# nGeigie_upper_boardV1_00.net
KiCad netlist of a schematic drawn in EAGLE
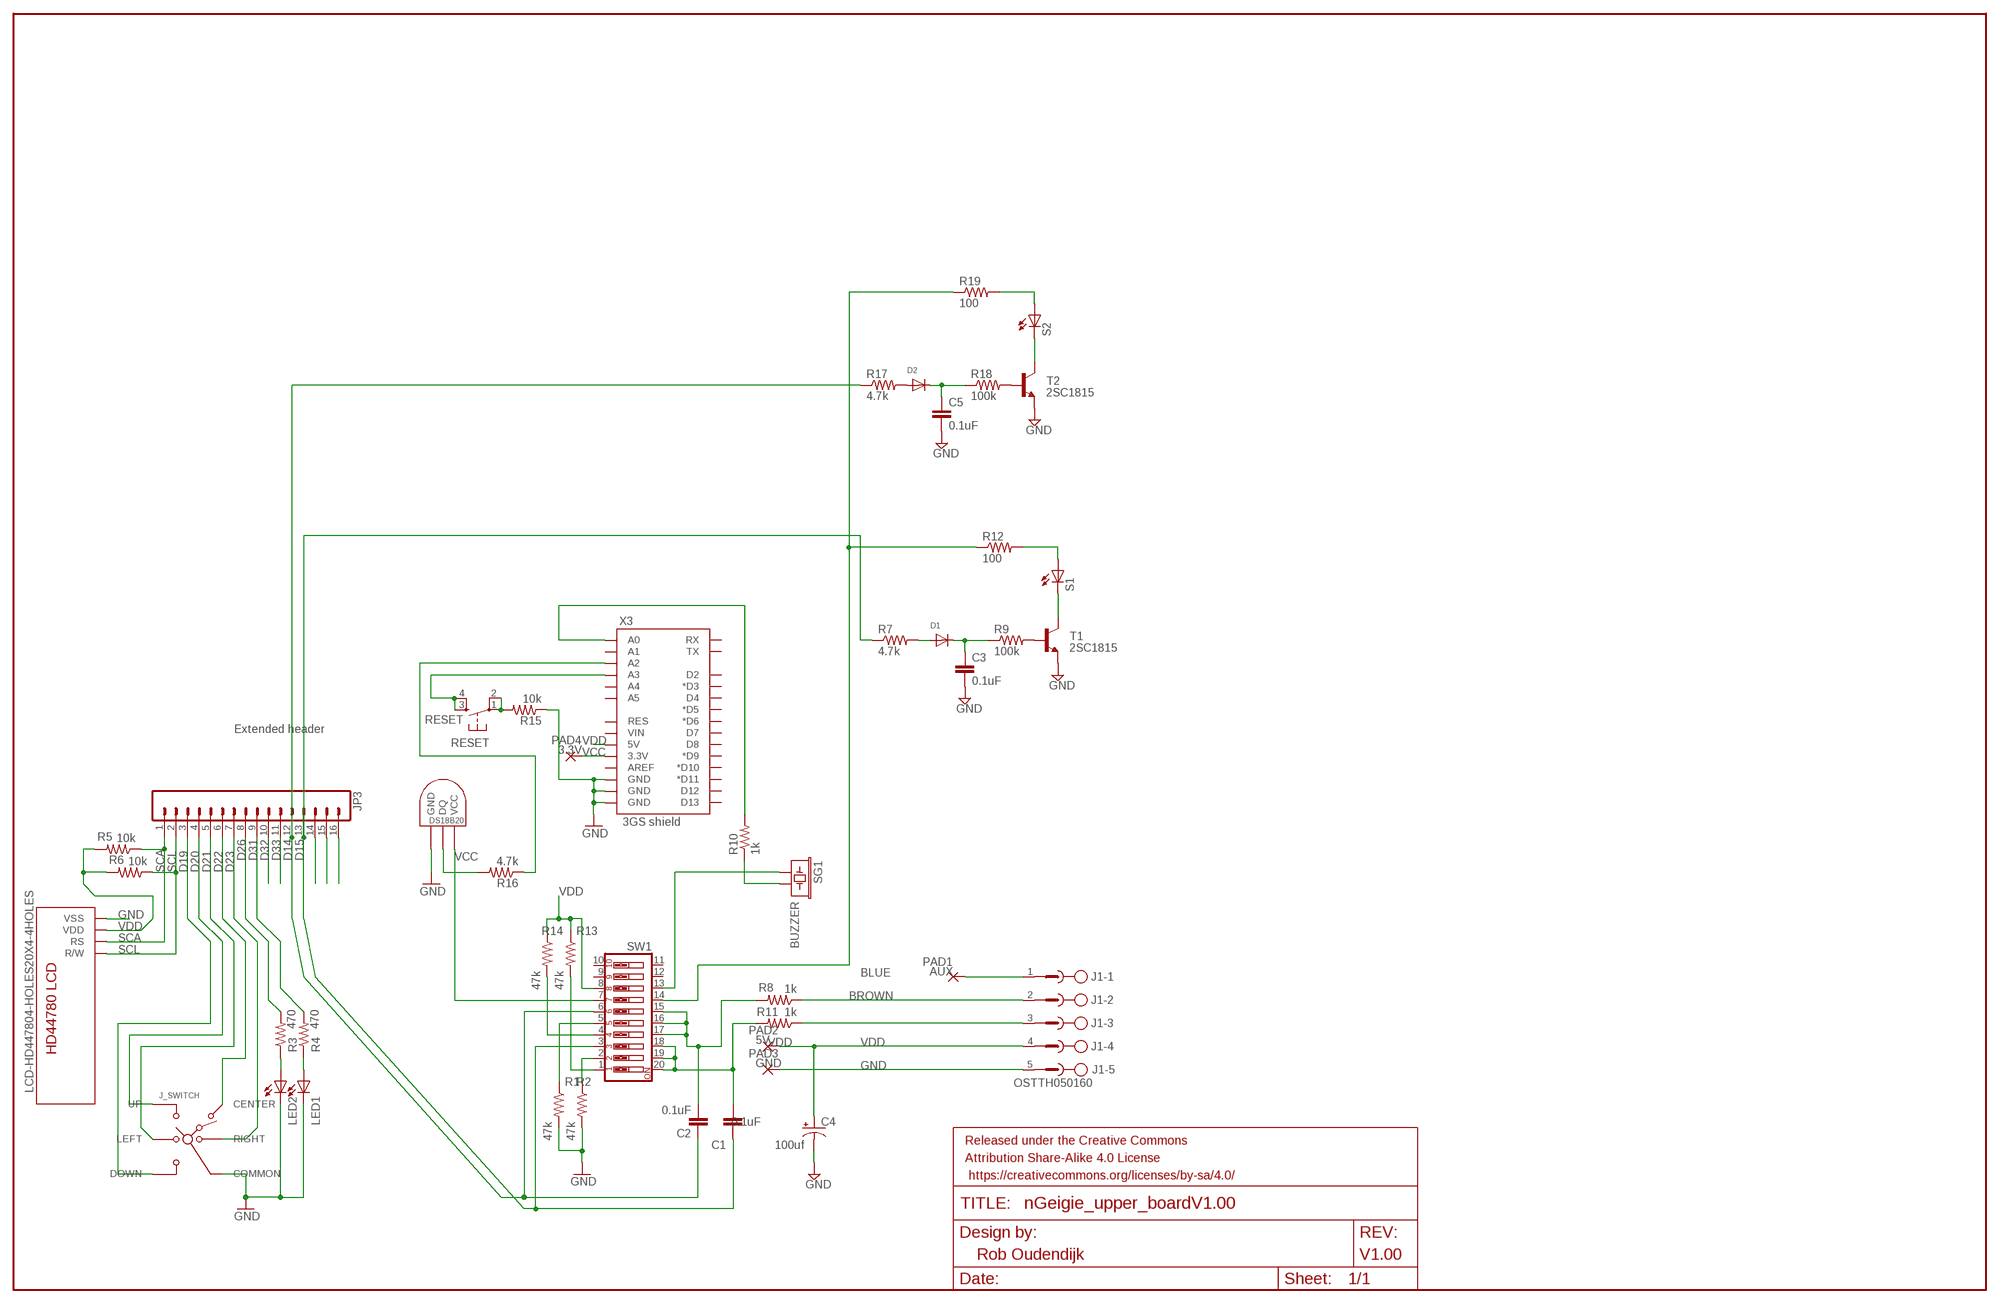
[diagram p0: schematic, sheet 1]

(export (version "E")
  (design (tool "Eeschema 10.0.6"))
  (components
    (comp (ref "C1")
      (value "0.1uF")
      (footprint "eagle-import:C025-024X044")
      (libsource (lib "eagle-import") (part "C-EU025-024X044"))
    )
    (comp (ref "C2")
      (value "0.1uF")
      (footprint "eagle-import:C025-024X044")
      (libsource (lib "eagle-import") (part "C-EU025-024X044"))
    )
    (comp (ref "C3")
      (value "0.1uF")
      (footprint "eagle-import:C025-024X044")
      (libsource (lib "eagle-import") (part "C-EU025-024X044"))
    )
    (comp (ref "C4")
      (value "100uf")
      (footprint "eagle-import:CPOL-RADIAL-100UF-25V")
      (libsource (lib "eagle-import") (part "CAP_POLPTH1"))
    )
    (comp (ref "C5")
      (value "0.1uF")
      (footprint "eagle-import:C025-024X044")
      (libsource (lib "eagle-import") (part "C-EU025-024X044"))
    )
    (comp (ref "D1")
      (value "DIODEDIODE_BIG")
      (footprint "eagle-import:DO41-10")
      (libsource (lib "eagle-import") (part "DIODEDIODE_BIG"))
    )
    (comp (ref "D2")
      (value "DIODEDIODE_BIG")
      (footprint "eagle-import:DO41-10")
      (libsource (lib "eagle-import") (part "DIODEDIODE_BIG"))
    )
    (comp (ref "FRAME1")
      (value "FRAME-LEDGER")
      (footprint "eagle-import:CREATIVE_COMMONS")
      (libsource (lib "eagle-import") (part "FRAME-LEDGER"))
    )
    (comp (ref "J1")
      (value "OSTTH050160")
      (footprint "eagle-import:EDSTL130-05")
      (libsource (lib "eagle-import") (part "OSTTH050160"))
    )
    (comp (ref "JP3")
      (value "Extended header")
      (footprint "eagle-import:1X16")
      (libsource (lib "eagle-import") (part "M16PTH"))
    )
    (comp (ref "J_SWITCH")
      (value "SKQUCAA010")
      (footprint "eagle-import:SKQU")
      (fields (field (name "MF") "ALPS"))
      (libsource (lib "eagle-import") (part "SKQUCAA010"))
    )
    (comp (ref "LED1")
      (value "LED3MM")
      (footprint "eagle-import:LED3MM")
      (libsource (lib "eagle-import") (part "LED3MM"))
    )
    (comp (ref "LED2")
      (value "LED3MM")
      (footprint "eagle-import:LED3MM")
      (libsource (lib "eagle-import") (part "LED3MM"))
    )
    (comp (ref "PAD1")
      (value "AUX")
      (footprint "eagle-import:2,15_1,0")
      (libsource (lib "eagle-import") (part "2,15/1,0"))
    )
    (comp (ref "PAD2")
      (value "5V")
      (footprint "eagle-import:2,15_1,0")
      (libsource (lib "eagle-import") (part "2,15/1,0"))
    )
    (comp (ref "PAD3")
      (value "GND")
      (footprint "eagle-import:2,15_1,0")
      (libsource (lib "eagle-import") (part "2,15/1,0"))
    )
    (comp (ref "PAD4")
      (value "3.3V")
      (footprint "eagle-import:2,15_1,0")
      (libsource (lib "eagle-import") (part "2,15/1,0"))
    )
    (comp (ref "R1")
      (value "47k")
      (footprint "eagle-import:0207_10")
      (libsource (lib "eagle-import") (part "resistor_R-US_0207/10"))
    )
    (comp (ref "R2")
      (value "47k")
      (footprint "eagle-import:0207_10")
      (libsource (lib "eagle-import") (part "resistor_R-US_0207/10"))
    )
    (comp (ref "R3")
      (value "470")
      (footprint "eagle-import:0207_10")
      (libsource (lib "eagle-import") (part "resistor_R-US_0207/10"))
    )
    (comp (ref "R4")
      (value "470")
      (footprint "eagle-import:0207_10")
      (libsource (lib "eagle-import") (part "resistor_R-US_0207/10"))
    )
    (comp (ref "R5")
      (value "10k")
      (footprint "eagle-import:0207_10")
      (libsource (lib "eagle-import") (part "R-US_0207/10"))
    )
    (comp (ref "R6")
      (value "10k")
      (footprint "eagle-import:0207_10")
      (libsource (lib "eagle-import") (part "R-US_0207/10"))
    )
    (comp (ref "R7")
      (value "4.7k")
      (footprint "eagle-import:0207_10")
      (libsource (lib "eagle-import") (part "rcl_R-US_0207/10"))
    )
    (comp (ref "R8")
      (value "1k")
      (footprint "eagle-import:0207_10")
      (libsource (lib "eagle-import") (part "resistor_R-US_0207/10"))
    )
    (comp (ref "R9")
      (value "100k")
      (footprint "eagle-import:0207_10")
      (libsource (lib "eagle-import") (part "rcl_R-US_0207/10"))
    )
    (comp (ref "R10")
      (value "1k")
      (footprint "eagle-import:0207_10")
      (libsource (lib "eagle-import") (part "resistor_R-US_0207/10"))
    )
    (comp (ref "R11")
      (value "1k")
      (footprint "eagle-import:0207_10")
      (libsource (lib "eagle-import") (part "resistor_R-US_0207/10"))
    )
    (comp (ref "R12")
      (value "100")
      (footprint "eagle-import:0207_10")
      (libsource (lib "eagle-import") (part "rcl_R-US_0207/10"))
    )
    (comp (ref "R13")
      (value "47k")
      (footprint "eagle-import:0207_10")
      (libsource (lib "eagle-import") (part "resistor_R-US_0207/10"))
    )
    (comp (ref "R14")
      (value "47k")
      (footprint "eagle-import:0207_10")
      (libsource (lib "eagle-import") (part "resistor_R-US_0207/10"))
    )
    (comp (ref "R15")
      (value "10k")
      (footprint "eagle-import:0207_10")
      (libsource (lib "eagle-import") (part "resistor_R-US_0207/10"))
    )
    (comp (ref "R16")
      (value "4.7k")
      (footprint "eagle-import:0207_10")
      (libsource (lib "eagle-import") (part "resistor_R-US_0207/10"))
    )
    (comp (ref "R17")
      (value "4.7k")
      (footprint "eagle-import:0207_10")
      (libsource (lib "eagle-import") (part "rcl_R-US_0207/10"))
    )
    (comp (ref "R18")
      (value "100k")
      (footprint "eagle-import:0207_10")
      (libsource (lib "eagle-import") (part "rcl_R-US_0207/10"))
    )
    (comp (ref "R19")
      (value "100")
      (footprint "eagle-import:0207_10")
      (libsource (lib "eagle-import") (part "rcl_R-US_0207/10"))
    )
    (comp (ref "RESET")
      (value "RESET")
      (footprint "eagle-import:DTS-6")
      (libsource (lib "eagle-import") (part "DTS-6"))
    )
    (comp (ref "S1")
      (value "LED3MM")
      (footprint "eagle-import:LED3MM")
      (libsource (lib "eagle-import") (part "LED3MM"))
    )
    (comp (ref "S2")
      (value "LED3MM")
      (footprint "eagle-import:LED3MM")
      (libsource (lib "eagle-import") (part "LED3MM"))
    )
    (comp (ref "SG1")
      (value "BUZZER")
      (footprint "eagle-import:BUZZER-12MM")
      (libsource (lib "eagle-import") (part "BUZZERPTH"))
    )
    (comp (ref "SW1")
      (value "SW_DIP-10")
      (footprint "eagle-import:EDG-10")
      (libsource (lib "eagle-import") (part "SW_DIP-10"))
    )
    (comp (ref "T1")
      (value "2SC1815")
      (footprint "eagle-import:TO92-ECB")
      (libsource (lib "eagle-import") (part "2SC1815"))
    )
    (comp (ref "T2")
      (value "2SC1815")
      (footprint "eagle-import:TO92-ECB")
      (libsource (lib "eagle-import") (part "2SC1815"))
    )
    (comp (ref "TEMP")
      (value "AVA_DS1820TO92")
      (footprint "eagle-import:AVA_DS1820")
      (libsource (lib "eagle-import") (part "AVA_DS1820TO92"))
    )
    (comp (ref "X1")
      (value "LCD-HD447804-HOLES20X4-4HOLES")
      (footprint "eagle-import:LCD-20X4-4HOLES")
      (libsource (lib "eagle-import") (part "LCD-HD4478020X4-4HOLES4-HOLES"))
    )
    (comp (ref "X3")
      (value "3GS shield")
      (footprint "eagle-import:DUEMILANOVE_SHIELD")
      (libsource (lib "eagle-import") (part "ARDUINO_SHIELDLABEL"))
    )
  )
  (nets
    (net (code "1") (name "/BLUE") (class "Default")
      (node (ref "J1") (pin "2") (pinfunction "SK_2") (pintype "passive"))
      (node (ref "R8") (pin "1") (pinfunction "1_1") (pintype "passive"))
    )
    (net (code "2") (name "/BROWN") (class "Default")
      (node (ref "J1") (pin "3") (pinfunction "SK_3") (pintype "passive"))
      (node (ref "R11") (pin "1") (pinfunction "1_1") (pintype "passive"))
    )
    (net (code "3") (name "/D14") (class "Default")
      (node (ref "C2") (pin "1") (pinfunction "1_1") (pintype "passive"))
      (node (ref "JP3") (pin "12") (pinfunction "12_12") (pintype "passive"))
      (node (ref "R17") (pin "1") (pinfunction "1_1") (pintype "passive"))
      (node (ref "SW1") (pin "6") (pinfunction "6_6") (pintype "passive"))
    )
    (net (code "4") (name "/D15") (class "Default")
      (node (ref "C1") (pin "1") (pinfunction "1_1") (pintype "passive"))
      (node (ref "JP3") (pin "13") (pinfunction "13_13") (pintype "passive"))
      (node (ref "R7") (pin "1") (pinfunction "1_1") (pintype "passive"))
      (node (ref "SW1") (pin "3") (pinfunction "3_3") (pintype "passive"))
    )
    (net (code "5") (name "/D19") (class "Default")
      (node (ref "JP3") (pin "3") (pinfunction "3_3") (pintype "passive"))
      (node (ref "J_SWITCH") (pin "DOWN") (pinfunction "DOWN_DOWN") (pintype "passive"))
    )
    (net (code "6") (name "/D20") (class "Default")
      (node (ref "JP3") (pin "4") (pinfunction "4_4") (pintype "passive"))
      (node (ref "J_SWITCH") (pin "UP") (pinfunction "UP_UP") (pintype "passive"))
    )
    (net (code "7") (name "/D21") (class "Default")
      (node (ref "JP3") (pin "5") (pinfunction "5_5") (pintype "passive"))
      (node (ref "J_SWITCH") (pin "LEFT") (pinfunction "LEFT_LEFT") (pintype "passive"))
    )
    (net (code "8") (name "/D22") (class "Default")
      (node (ref "JP3") (pin "6") (pinfunction "6_6") (pintype "passive"))
      (node (ref "J_SWITCH") (pin "CENTER") (pinfunction "CENTER_CENTER") (pintype "passive"))
    )
    (net (code "9") (name "/D23") (class "Default")
      (node (ref "JP3") (pin "7") (pinfunction "7_7") (pintype "passive"))
      (node (ref "J_SWITCH") (pin "RIGHT") (pinfunction "RIGHT_RIGHT") (pintype "passive"))
    )
    (net (code "10") (name "/D26") (class "Default")
      (node (ref "JP3") (pin "8") (pinfunction "8_8") (pintype "passive"))
      (node (ref "R3") (pin "2") (pinfunction "2_2") (pintype "passive"))
    )
    (net (code "11") (name "/D31") (class "Default")
      (node (ref "JP3") (pin "9") (pinfunction "9_9") (pintype "passive"))
      (node (ref "R4") (pin "2") (pinfunction "2_2") (pintype "passive"))
    )
    (net (code "12") (name "/D32") (class "Default")
      (node (ref "JP3") (pin "10") (pinfunction "10_10") (pintype "passive"))
    )
    (net (code "13") (name "/D33") (class "Default")
      (node (ref "JP3") (pin "11") (pinfunction "11_11") (pintype "passive"))
    )
    (net (code "14") (name "/SCA") (class "Default")
      (node (ref "JP3") (pin "1") (pinfunction "1_1") (pintype "passive"))
      (node (ref "R5") (pin "1") (pinfunction "1_1") (pintype "passive"))
      (node (ref "X1") (pin "P$15") (pinfunction "RS_P$15") (pintype "input"))
    )
    (net (code "15") (name "/SCL") (class "Default")
      (node (ref "JP3") (pin "2") (pinfunction "2_2") (pintype "passive"))
      (node (ref "R6") (pin "1") (pinfunction "1_1") (pintype "passive"))
      (node (ref "X1") (pin "P$16") (pinfunction "R/W_P$16") (pintype "input"))
    )
    (net (code "16") (name "/VCC") (class "Default")
      (node (ref "PAD4") (pin "1") (pinfunction "P_1") (pintype "passive"))
      (node (ref "SW1") (pin "7") (pinfunction "7_7") (pintype "passive"))
      (node (ref "TEMP") (pin "VDD") (pinfunction "VCC_VDD") (pintype "power_in"))
      (node (ref "X3") (pin "3.3V") (pinfunction "3.3V_3.3V") (pintype "bidirectional"))
    )
    (net (code "17") (name "/VDD") (class "Default")
      (node (ref "C4") (pin "2") (pinfunction "+_2") (pintype "passive"))
      (node (ref "J1") (pin "4") (pinfunction "SK_4") (pintype "passive"))
      (node (ref "PAD2") (pin "1") (pinfunction "P_1") (pintype "passive"))
      (node (ref "R13") (pin "1") (pinfunction "1_1") (pintype "passive"))
      (node (ref "R14") (pin "1") (pinfunction "1_1") (pintype "passive"))
      (node (ref "R5") (pin "2") (pinfunction "2_2") (pintype "passive"))
      (node (ref "R6") (pin "2") (pinfunction "2_2") (pintype "passive"))
      (node (ref "SW1") (pin "8") (pinfunction "8_8") (pintype "passive"))
      (node (ref "X1") (pin "P$14") (pinfunction "VDD_P$14") (pintype "power_in"))
      (node (ref "X3") (pin "5V") (pinfunction "5V_5V") (pintype "bidirectional"))
    )
    (net (code "18") (name "GND") (class "Default")
      (node (ref "C3") (pin "2") (pinfunction "2_2") (pintype "passive"))
      (node (ref "C4") (pin "1") (pinfunction "-_1") (pintype "passive"))
      (node (ref "C5") (pin "2") (pinfunction "2_2") (pintype "passive"))
      (node (ref "J1") (pin "5") (pinfunction "SK_5") (pintype "passive"))
      (node (ref "J_SWITCH") (pin "COMMON") (pinfunction "COMMON_COMMON") (pintype "power_in"))
      (node (ref "LED1") (pin "K") (pinfunction "C_K") (pintype "passive"))
      (node (ref "LED2") (pin "K") (pinfunction "C_K") (pintype "passive"))
      (node (ref "PAD3") (pin "1") (pinfunction "P_1") (pintype "passive"))
      (node (ref "R1") (pin "2") (pinfunction "2_2") (pintype "passive"))
      (node (ref "R15") (pin "1") (pinfunction "1_1") (pintype "passive"))
      (node (ref "R2") (pin "2") (pinfunction "2_2") (pintype "passive"))
      (node (ref "T1") (pin "E") (pinfunction "E_E") (pintype "passive"))
      (node (ref "T2") (pin "E") (pinfunction "E_E") (pintype "passive"))
      (node (ref "TEMP") (pin "GND") (pinfunction "GND_GND") (pintype "power_in"))
      (node (ref "X1") (pin "P$13") (pinfunction "VSS_P$13") (pintype "power_in"))
      (node (ref "X3") (pin "GND@0") (pinfunction "GND_GND@0") (pintype "bidirectional"))
      (node (ref "X3") (pin "GND@1") (pinfunction "GND_GND@1") (pintype "bidirectional"))
      (node (ref "X3") (pin "GND@2") (pinfunction "GND_GND@2") (pintype "bidirectional"))
    )
    (net (code "19") (name "Net-(C1-Pad2)") (class "Default")
      (node (ref "C1") (pin "2") (pinfunction "2_2") (pintype "passive"))
      (node (ref "R11") (pin "2") (pinfunction "2_2") (pintype "passive"))
      (node (ref "SW1") (pin "18") (pinfunction "18_18") (pintype "passive"))
      (node (ref "SW1") (pin "19") (pinfunction "19_19") (pintype "passive"))
      (node (ref "SW1") (pin "20") (pinfunction "20_20") (pintype "passive"))
    )
    (net (code "20") (name "Net-(C2-Pad2)") (class "Default")
      (node (ref "C2") (pin "2") (pinfunction "2_2") (pintype "passive"))
      (node (ref "R8") (pin "2") (pinfunction "2_2") (pintype "passive"))
      (node (ref "SW1") (pin "15") (pinfunction "15_15") (pintype "passive"))
      (node (ref "SW1") (pin "16") (pinfunction "16_16") (pintype "passive"))
      (node (ref "SW1") (pin "17") (pinfunction "17_17") (pintype "passive"))
    )
    (net (code "21") (name "Net-(C3-Pad1)") (class "Default")
      (node (ref "C3") (pin "1") (pinfunction "1_1") (pintype "passive"))
      (node (ref "D1") (pin "C") (pinfunction "C_C") (pintype "passive"))
      (node (ref "R9") (pin "1") (pinfunction "1_1") (pintype "passive"))
    )
    (net (code "22") (name "Net-(C5-Pad1)") (class "Default")
      (node (ref "C5") (pin "1") (pinfunction "1_1") (pintype "passive"))
      (node (ref "D2") (pin "C") (pinfunction "C_C") (pintype "passive"))
      (node (ref "R18") (pin "1") (pinfunction "1_1") (pintype "passive"))
    )
    (net (code "23") (name "Net-(D1-PadA)") (class "Default")
      (node (ref "D1") (pin "A") (pinfunction "A_A") (pintype "passive"))
      (node (ref "R7") (pin "2") (pinfunction "2_2") (pintype "passive"))
    )
    (net (code "24") (name "Net-(D2-PadA)") (class "Default")
      (node (ref "D2") (pin "A") (pinfunction "A_A") (pintype "passive"))
      (node (ref "R17") (pin "2") (pinfunction "2_2") (pintype "passive"))
    )
    (net (code "25") (name "Net-(J1A-SK)") (class "Default")
      (node (ref "J1") (pin "1") (pinfunction "SK_1") (pintype "passive"))
      (node (ref "PAD1") (pin "1") (pinfunction "P_1") (pintype "passive"))
    )
    (net (code "26") (name "Net-(LED1-PadA)") (class "Default")
      (node (ref "LED1") (pin "A") (pinfunction "A_A") (pintype "passive"))
      (node (ref "R4") (pin "1") (pinfunction "1_1") (pintype "passive"))
    )
    (net (code "27") (name "Net-(LED2-PadA)") (class "Default")
      (node (ref "LED2") (pin "A") (pinfunction "A_A") (pintype "passive"))
      (node (ref "R3") (pin "1") (pinfunction "1_1") (pintype "passive"))
    )
    (net (code "28") (name "Net-(R1-Pad1)") (class "Default")
      (node (ref "R1") (pin "1") (pinfunction "1_1") (pintype "passive"))
      (node (ref "SW1") (pin "5") (pinfunction "5_5") (pintype "passive"))
    )
    (net (code "29") (name "Net-(R2-Pad1)") (class "Default")
      (node (ref "R2") (pin "1") (pinfunction "1_1") (pintype "passive"))
      (node (ref "SW1") (pin "2") (pinfunction "2_2") (pintype "passive"))
    )
    (net (code "30") (name "Net-(R9-Pad2)") (class "Default")
      (node (ref "R9") (pin "2") (pinfunction "2_2") (pintype "passive"))
      (node (ref "T1") (pin "B") (pinfunction "B_B") (pintype "passive"))
    )
    (net (code "31") (name "Net-(R10-Pad2)") (class "Default")
      (node (ref "R10") (pin "2") (pinfunction "2_2") (pintype "passive"))
      (node (ref "X3") (pin "A0") (pinfunction "A0_A0") (pintype "bidirectional"))
    )
    (net (code "32") (name "Net-(R12-Pad1)") (class "Default")
      (node (ref "R12") (pin "1") (pinfunction "1_1") (pintype "passive"))
      (node (ref "R19") (pin "1") (pinfunction "1_1") (pintype "passive"))
      (node (ref "SW1") (pin "14") (pinfunction "14_14") (pintype "passive"))
    )
    (net (code "33") (name "Net-(R12-Pad2)") (class "Default")
      (node (ref "R12") (pin "2") (pinfunction "2_2") (pintype "passive"))
      (node (ref "S1") (pin "A") (pinfunction "A_A") (pintype "passive"))
    )
    (net (code "34") (name "Net-(R13-Pad2)") (class "Default")
      (node (ref "R13") (pin "2") (pinfunction "2_2") (pintype "passive"))
      (node (ref "SW1") (pin "1") (pinfunction "1_1") (pintype "passive"))
    )
    (net (code "35") (name "Net-(R14-Pad2)") (class "Default")
      (node (ref "R14") (pin "2") (pinfunction "2_2") (pintype "passive"))
      (node (ref "SW1") (pin "4") (pinfunction "4_4") (pintype "passive"))
    )
    (net (code "36") (name "Net-(R15-Pad2)") (class "Default")
      (node (ref "R15") (pin "2") (pinfunction "2_2") (pintype "passive"))
      (node (ref "RESET") (pin "1") (pinfunction "1_1") (pintype "passive"))
      (node (ref "RESET") (pin "2") (pinfunction "2_2") (pintype "passive"))
    )
    (net (code "37") (name "Net-(R16-Pad1)") (class "Default")
      (node (ref "R16") (pin "1") (pinfunction "1_1") (pintype "passive"))
      (node (ref "X3") (pin "A2") (pinfunction "A2_A2") (pintype "bidirectional"))
    )
    (net (code "38") (name "Net-(R16-Pad2)") (class "Default")
      (node (ref "R16") (pin "2") (pinfunction "2_2") (pintype "passive"))
      (node (ref "TEMP") (pin "DQ") (pinfunction "DQ_DQ") (pintype "bidirectional"))
    )
    (net (code "39") (name "Net-(R18-Pad2)") (class "Default")
      (node (ref "R18") (pin "2") (pinfunction "2_2") (pintype "passive"))
      (node (ref "T2") (pin "B") (pinfunction "B_B") (pintype "passive"))
    )
    (net (code "40") (name "Net-(R19-Pad2)") (class "Default")
      (node (ref "R19") (pin "2") (pinfunction "2_2") (pintype "passive"))
      (node (ref "S2") (pin "A") (pinfunction "A_A") (pintype "passive"))
    )
    (net (code "41") (name "Net-(RESET-Pad3)") (class "Default")
      (node (ref "RESET") (pin "3") (pinfunction "3_3") (pintype "passive"))
      (node (ref "RESET") (pin "4") (pinfunction "4_4") (pintype "passive"))
      (node (ref "X3") (pin "A3") (pinfunction "A3_A3") (pintype "bidirectional"))
    )
    (net (code "42") (name "Net-(S1-C)") (class "Default")
      (node (ref "S1") (pin "K") (pinfunction "C_K") (pintype "passive"))
      (node (ref "T1") (pin "C") (pinfunction "C_C") (pintype "passive"))
    )
    (net (code "43") (name "Net-(S2-C)") (class "Default")
      (node (ref "S2") (pin "K") (pinfunction "C_K") (pintype "passive"))
      (node (ref "T2") (pin "C") (pinfunction "C_C") (pintype "passive"))
    )
    (net (code "44") (name "Net-(SG1-1)") (class "Default")
      (node (ref "SG1") (pin "+") (pinfunction "1_+") (pintype "passive"))
      (node (ref "SW1") (pin "13") (pinfunction "13_13") (pintype "passive"))
    )
    (net (code "45") (name "Net-(SG1-2)") (class "Default")
      (node (ref "R10") (pin "1") (pinfunction "1_1") (pintype "passive"))
      (node (ref "SG1") (pin "-") (pinfunction "2_-") (pintype "passive"))
    )
    (net (code "46") (name "unconnected-(JP3-Pad14)") (class "Default")
      (node (ref "JP3") (pin "14") (pinfunction "14_14") (pintype "passive"))
    )
    (net (code "47") (name "unconnected-(JP3-Pad15)") (class "Default")
      (node (ref "JP3") (pin "15") (pinfunction "15_15") (pintype "passive"))
    )
    (net (code "48") (name "unconnected-(JP3-Pad16)") (class "Default")
      (node (ref "JP3") (pin "16") (pinfunction "16_16") (pintype "passive"))
    )
    (net (code "49") (name "unconnected-(SW1-Pad9)") (class "Default")
      (node (ref "SW1") (pin "9") (pinfunction "9_9") (pintype "passive"))
    )
    (net (code "50") (name "unconnected-(SW1-Pad10)") (class "Default")
      (node (ref "SW1") (pin "10") (pinfunction "10_10") (pintype "passive"))
    )
    (net (code "51") (name "unconnected-(SW1-Pad11)") (class "Default")
      (node (ref "SW1") (pin "11") (pinfunction "11_11") (pintype "passive"))
    )
    (net (code "52") (name "unconnected-(SW1-Pad12)") (class "Default")
      (node (ref "SW1") (pin "12") (pinfunction "12_12") (pintype "passive"))
    )
    (net (code "53") (name "unconnected-(X3-*D3-PadD3)") (class "Default")
      (node (ref "X3") (pin "D3") (pinfunction "*D3_D3") (pintype "bidirectional"))
    )
    (net (code "54") (name "unconnected-(X3-*D5-PadD5)") (class "Default")
      (node (ref "X3") (pin "D5") (pinfunction "*D5_D5") (pintype "bidirectional"))
    )
    (net (code "55") (name "unconnected-(X3-*D6-PadD6)") (class "Default")
      (node (ref "X3") (pin "D6") (pinfunction "*D6_D6") (pintype "bidirectional"))
    )
    (net (code "56") (name "unconnected-(X3-*D9-PadD9)") (class "Default")
      (node (ref "X3") (pin "D9") (pinfunction "*D9_D9") (pintype "bidirectional"))
    )
    (net (code "57") (name "unconnected-(X3-*D10-PadD10)") (class "Default")
      (node (ref "X3") (pin "D10") (pinfunction "*D10_D10") (pintype "bidirectional"))
    )
    (net (code "58") (name "unconnected-(X3-*D11-PadD11)") (class "Default")
      (node (ref "X3") (pin "D11") (pinfunction "*D11_D11") (pintype "bidirectional"))
    )
    (net (code "59") (name "unconnected-(X3-PadA1)") (class "Default")
      (node (ref "X3") (pin "A1") (pinfunction "A1_A1") (pintype "bidirectional"))
    )
    (net (code "60") (name "unconnected-(X3-PadA4)") (class "Default")
      (node (ref "X3") (pin "A4") (pinfunction "A4_A4") (pintype "bidirectional"))
    )
    (net (code "61") (name "unconnected-(X3-PadA5)") (class "Default")
      (node (ref "X3") (pin "A5") (pinfunction "A5_A5") (pintype "bidirectional"))
    )
    (net (code "62") (name "unconnected-(X3-PadAREF)") (class "Default")
      (node (ref "X3") (pin "AREF") (pinfunction "AREF_AREF") (pintype "bidirectional"))
    )
    (net (code "63") (name "unconnected-(X3-PadD2)") (class "Default")
      (node (ref "X3") (pin "D2") (pinfunction "D2_D2") (pintype "bidirectional"))
    )
    (net (code "64") (name "unconnected-(X3-PadD4)") (class "Default")
      (node (ref "X3") (pin "D4") (pinfunction "D4_D4") (pintype "bidirectional"))
    )
    (net (code "65") (name "unconnected-(X3-PadD7)") (class "Default")
      (node (ref "X3") (pin "D7") (pinfunction "D7_D7") (pintype "bidirectional"))
    )
    (net (code "66") (name "unconnected-(X3-PadD8)") (class "Default")
      (node (ref "X3") (pin "D8") (pinfunction "D8_D8") (pintype "bidirectional"))
    )
    (net (code "67") (name "unconnected-(X3-PadD12)") (class "Default")
      (node (ref "X3") (pin "D12") (pinfunction "D12_D12") (pintype "bidirectional"))
    )
    (net (code "68") (name "unconnected-(X3-PadD13)") (class "Default")
      (node (ref "X3") (pin "D13") (pinfunction "D13_D13") (pintype "bidirectional"))
    )
    (net (code "69") (name "unconnected-(X3-PadRES)") (class "Default")
      (node (ref "X3") (pin "RES") (pinfunction "RES_RES") (pintype "bidirectional"))
    )
    (net (code "70") (name "unconnected-(X3-PadRX)") (class "Default")
      (node (ref "X3") (pin "RX") (pinfunction "RX_RX") (pintype "bidirectional"))
    )
    (net (code "71") (name "unconnected-(X3-PadTX)") (class "Default")
      (node (ref "X3") (pin "TX") (pinfunction "TX_TX") (pintype "bidirectional"))
    )
    (net (code "72") (name "unconnected-(X3-PadVIN)") (class "Default")
      (node (ref "X3") (pin "VIN") (pinfunction "VIN_VIN") (pintype "bidirectional"))
    )
  )
)
